# DueShield2.net
KiCad netlist of a schematic drawn in EAGLE
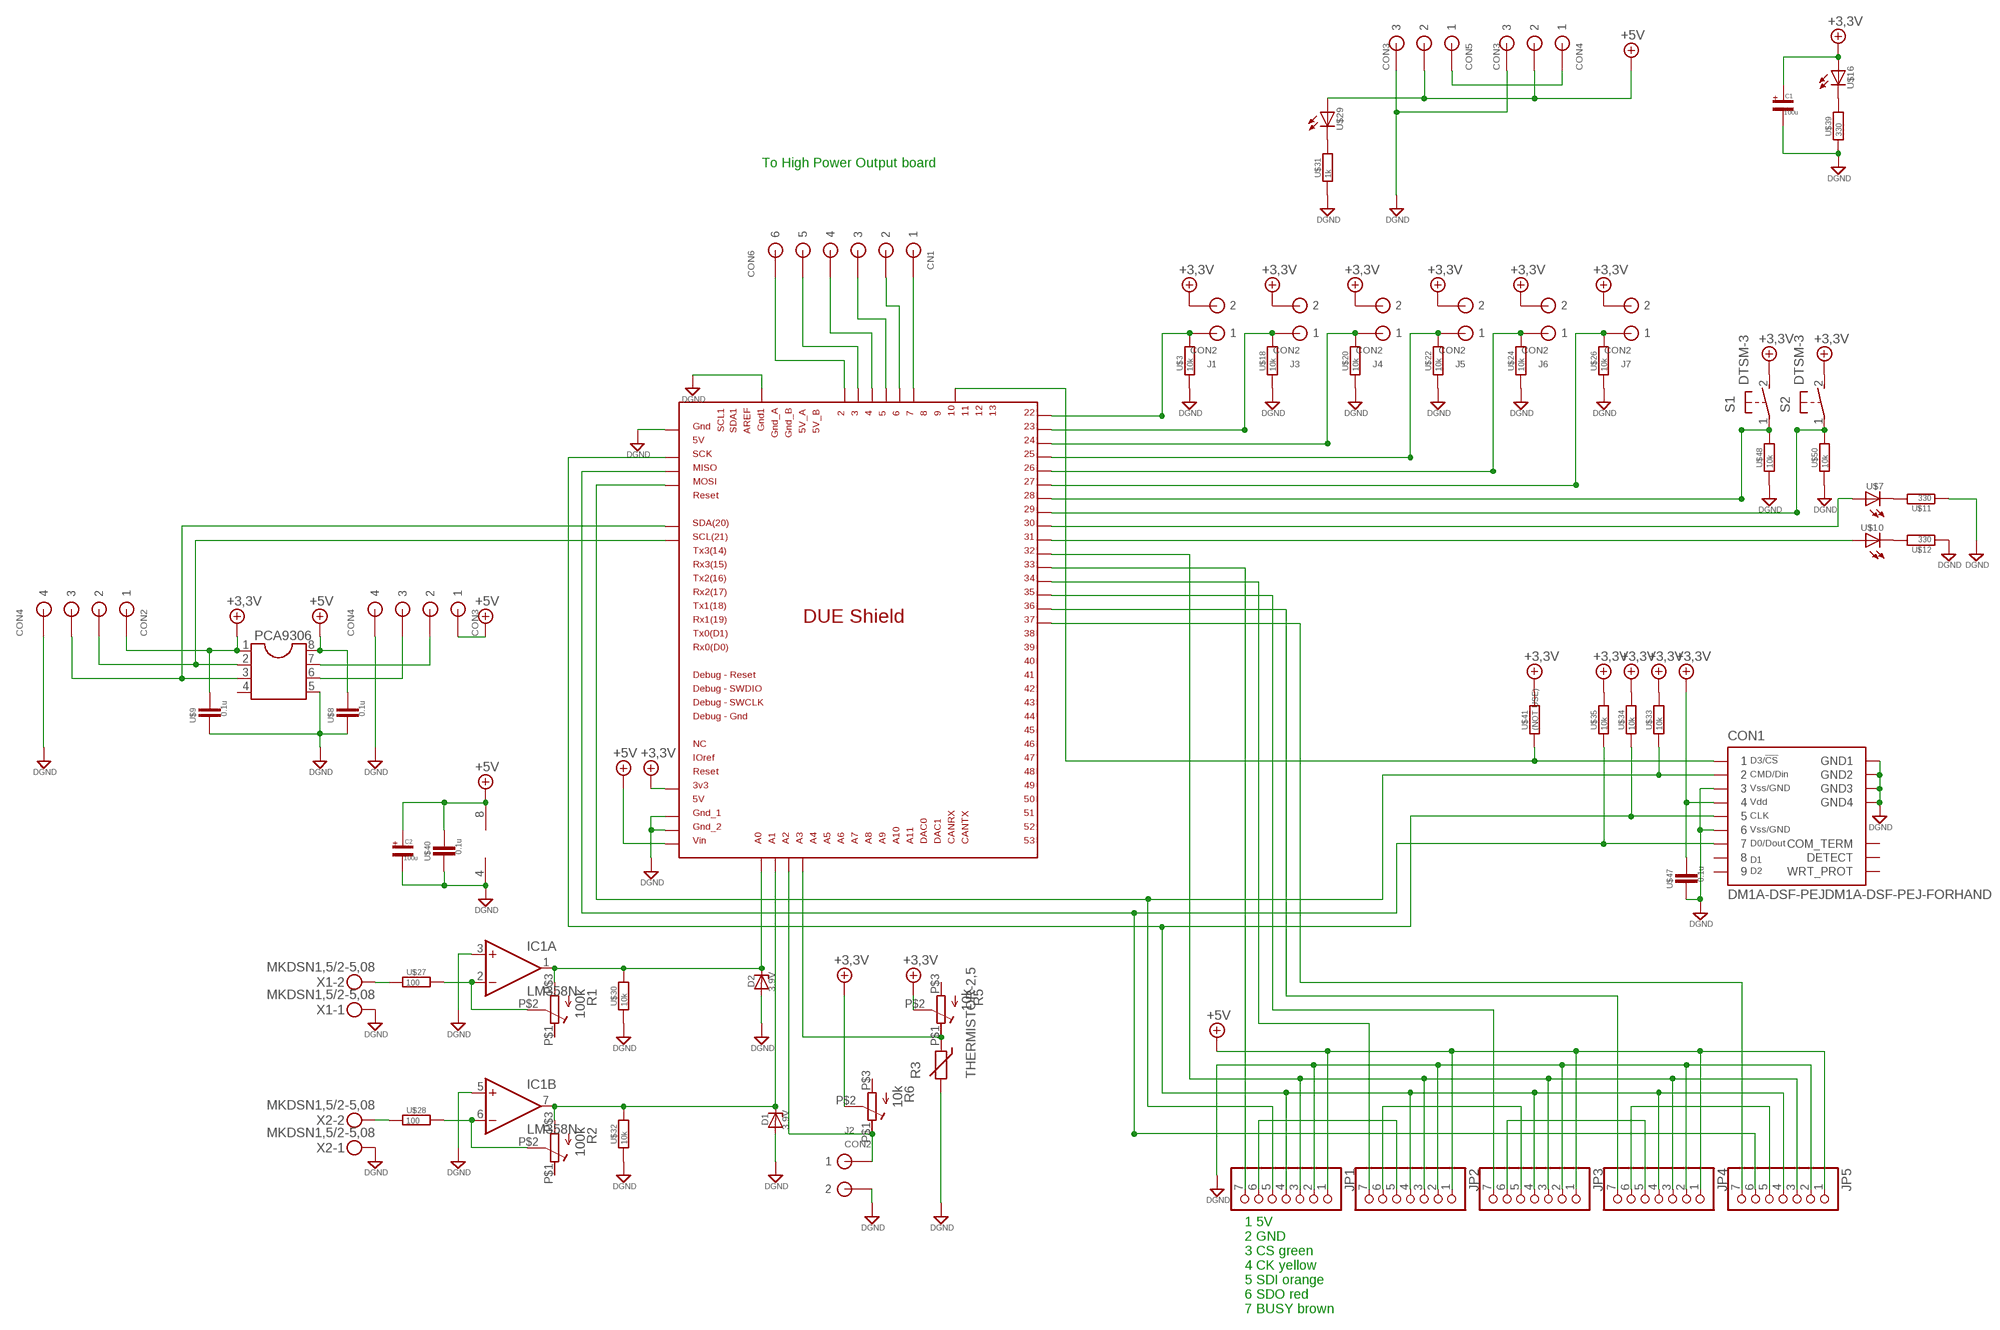
[diagram p0: schematic, sheet 1]

(export (version "E")
  (design (tool "Eeschema 10.0.6"))
  (components
    (comp (ref "C1")
      (value "100u")
      (footprint "eagle-import:D=1,φ=6")
      (libsource (lib "eagle-import") (part "コンデンサ(電解)E2.5-6"))
    )
    (comp (ref "C2")
      (value "100u")
      (footprint "eagle-import:D=1,φ=6")
      (libsource (lib "eagle-import") (part "コンデンサ(電解)E2.5-6"))
    )
    (comp (ref "CN1")
      (value "CON6")
      (footprint "eagle-import:CON6")
      (libsource (lib "eagle-import") (part "CON6"))
    )
    (comp (ref "CON1")
      (value "DM1A-DSF-PEJDM1A-DSF-PEJ-FORHAND")
      (footprint "eagle-import:DM1A-DSF-PEJ-FORHAND")
      (libsource (lib "eagle-import") (part "DM1A-DSF-PEJDM1A-DSF-PEJ-FORHAND"))
    )
    (comp (ref "CON2")
      (value "CON4")
      (footprint "eagle-import:CON4")
      (libsource (lib "eagle-import") (part "CON4"))
    )
    (comp (ref "CON3")
      (value "CON4")
      (footprint "eagle-import:CON4")
      (libsource (lib "eagle-import") (part "CON4"))
    )
    (comp (ref "CON4")
      (value "CON3")
      (footprint "eagle-import:CON3")
      (libsource (lib "eagle-import") (part "CON3"))
    )
    (comp (ref "CON5")
      (value "CON3")
      (footprint "eagle-import:CON3")
      (libsource (lib "eagle-import") (part "CON3"))
    )
    (comp (ref "D1")
      (value "3.9V")
      (footprint "eagle-import:SMD1206")
      (libsource (lib "eagle-import") (part "(汎用)ツェナーダイオード"))
    )
    (comp (ref "D2")
      (value "3.9V")
      (footprint "eagle-import:SMD1206")
      (libsource (lib "eagle-import") (part "(汎用)ツェナーダイオード"))
    )
    (comp (ref "IC1")
      (value "LM358N")
      (footprint "eagle-import:DIL08")
      (libsource (lib "eagle-import") (part "LM358N"))
    )
    (comp (ref "J1")
      (value "CON2")
      (footprint "eagle-import:CON2")
      (libsource (lib "eagle-import") (part "CON2"))
    )
    (comp (ref "J2")
      (value "CON2")
      (footprint "eagle-import:CON2")
      (libsource (lib "eagle-import") (part "CON2"))
    )
    (comp (ref "J3")
      (value "CON2")
      (footprint "eagle-import:CON2")
      (libsource (lib "eagle-import") (part "CON2"))
    )
    (comp (ref "J4")
      (value "CON2")
      (footprint "eagle-import:CON2")
      (libsource (lib "eagle-import") (part "CON2"))
    )
    (comp (ref "J5")
      (value "CON2")
      (footprint "eagle-import:CON2")
      (libsource (lib "eagle-import") (part "CON2"))
    )
    (comp (ref "J6")
      (value "CON2")
      (footprint "eagle-import:CON2")
      (libsource (lib "eagle-import") (part "CON2"))
    )
    (comp (ref "J7")
      (value "CON2")
      (footprint "eagle-import:CON2")
      (libsource (lib "eagle-import") (part "CON2"))
    )
    (comp (ref "JP1")
      (value "PINHD-1X7")
      (footprint "eagle-import:1X07")
      (libsource (lib "eagle-import") (part "PINHD-1X7"))
    )
    (comp (ref "JP2")
      (value "PINHD-1X7")
      (footprint "eagle-import:1X07")
      (libsource (lib "eagle-import") (part "PINHD-1X7"))
    )
    (comp (ref "JP3")
      (value "PINHD-1X7")
      (footprint "eagle-import:1X07")
      (libsource (lib "eagle-import") (part "PINHD-1X7"))
    )
    (comp (ref "JP4")
      (value "PINHD-1X7")
      (footprint "eagle-import:1X07")
      (libsource (lib "eagle-import") (part "PINHD-1X7"))
    )
    (comp (ref "JP5")
      (value "PINHD-1X7")
      (footprint "eagle-import:1X07")
      (libsource (lib "eagle-import") (part "PINHD-1X7"))
    )
    (comp (ref "PCA9306")
      (value "DIL8")
      (footprint "eagle-import:DIL08")
      (libsource (lib "eagle-import") (part "DIL8"))
    )
    (comp (ref "R1")
      (value "100k")
      (footprint "eagle-import:GF063PB")
      (libsource (lib "eagle-import") (part "抵抗(可変)"))
    )
    (comp (ref "R2")
      (value "100k")
      (footprint "eagle-import:GF063PB")
      (libsource (lib "eagle-import") (part "抵抗(可変)"))
    )
    (comp (ref "R3")
      (value "THERMISTOR-2,5")
      (footprint "eagle-import:RS-2,5")
      (libsource (lib "eagle-import") (part "THERMISTOR-2,5"))
    )
    (comp (ref "R5")
      (value "10k")
      (footprint "eagle-import:GF063PB")
      (libsource (lib "eagle-import") (part "抵抗(可変)"))
    )
    (comp (ref "R6")
      (value "10k")
      (footprint "eagle-import:GF063PB")
      (libsource (lib "eagle-import") (part "抵抗(可変)"))
    )
    (comp (ref "S1")
      (value "DTSM-3")
      (footprint "eagle-import:DTSM-3")
      (libsource (lib "eagle-import") (part "DTSM-3"))
    )
    (comp (ref "S2")
      (value "DTSM-3")
      (footprint "eagle-import:DTSM-3")
      (libsource (lib "eagle-import") (part "DTSM-3"))
    )
    (comp (ref "U$1")
      (value "DUE(3DPRINTER2)")
      (footprint "eagle-import:DUE(3DPRITNER2)")
      (libsource (lib "eagle-import") (part "DUE(3DPRINTER2)"))
    )
    (comp (ref "U$3")
      (value "10k")
      (footprint "eagle-import:0805(JIS2012)HAND")
      (libsource (lib "eagle-import") (part "抵抗0805"))
    )
    (comp (ref "U$7")
      (value "LED(砲弾型)3")
      (footprint "eagle-import:LED3MM")
      (libsource (lib "eagle-import") (part "LED(砲弾型)3"))
    )
    (comp (ref "U$8")
      (value "0.1u")
      (footprint "eagle-import:0805(JIS2012)HAND")
      (libsource (lib "eagle-import") (part "コンデンサ0805"))
    )
    (comp (ref "U$9")
      (value "0.1u")
      (footprint "eagle-import:0805(JIS2012)HAND")
      (libsource (lib "eagle-import") (part "コンデンサ0805"))
    )
    (comp (ref "U$10")
      (value "LED(砲弾型)3")
      (footprint "eagle-import:LED3MM")
      (libsource (lib "eagle-import") (part "LED(砲弾型)3"))
    )
    (comp (ref "U$11")
      (value "330")
      (footprint "eagle-import:0805(JIS2012)HAND")
      (libsource (lib "eagle-import") (part "抵抗0805"))
    )
    (comp (ref "U$12")
      (value "330")
      (footprint "eagle-import:0805(JIS2012)HAND")
      (libsource (lib "eagle-import") (part "抵抗0805"))
    )
    (comp (ref "U$16")
      (value "LED(砲弾型)3")
      (footprint "eagle-import:LED3MM")
      (libsource (lib "eagle-import") (part "LED(砲弾型)3"))
    )
    (comp (ref "U$18")
      (value "10k")
      (footprint "eagle-import:0805(JIS2012)HAND")
      (libsource (lib "eagle-import") (part "抵抗0805"))
    )
    (comp (ref "U$20")
      (value "10k")
      (footprint "eagle-import:0805(JIS2012)HAND")
      (libsource (lib "eagle-import") (part "抵抗0805"))
    )
    (comp (ref "U$22")
      (value "10k")
      (footprint "eagle-import:0805(JIS2012)HAND")
      (libsource (lib "eagle-import") (part "抵抗0805"))
    )
    (comp (ref "U$24")
      (value "10k")
      (footprint "eagle-import:0805(JIS2012)HAND")
      (libsource (lib "eagle-import") (part "抵抗0805"))
    )
    (comp (ref "U$26")
      (value "10k")
      (footprint "eagle-import:0805(JIS2012)HAND")
      (libsource (lib "eagle-import") (part "抵抗0805"))
    )
    (comp (ref "U$27")
      (value "100")
      (footprint "eagle-import:0805(JIS2012)HAND")
      (libsource (lib "eagle-import") (part "抵抗0805"))
    )
    (comp (ref "U$28")
      (value "100")
      (footprint "eagle-import:0805(JIS2012)HAND")
      (libsource (lib "eagle-import") (part "抵抗0805"))
    )
    (comp (ref "U$29")
      (value "LED(砲弾型)3")
      (footprint "eagle-import:LED3MM")
      (libsource (lib "eagle-import") (part "LED(砲弾型)3"))
    )
    (comp (ref "U$30")
      (value "10k")
      (footprint "eagle-import:0805(JIS2012)HAND")
      (libsource (lib "eagle-import") (part "抵抗0805"))
    )
    (comp (ref "U$31")
      (value "1k")
      (footprint "eagle-import:0805(JIS2012)HAND")
      (libsource (lib "eagle-import") (part "抵抗0805"))
    )
    (comp (ref "U$32")
      (value "10k")
      (footprint "eagle-import:0805(JIS2012)HAND")
      (libsource (lib "eagle-import") (part "抵抗0805"))
    )
    (comp (ref "U$33")
      (value "10k")
      (footprint "eagle-import:0805(JIS2012)HAND")
      (libsource (lib "eagle-import") (part "抵抗0805"))
    )
    (comp (ref "U$34")
      (value "10k")
      (footprint "eagle-import:0805(JIS2012)HAND")
      (libsource (lib "eagle-import") (part "抵抗0805"))
    )
    (comp (ref "U$35")
      (value "10k")
      (footprint "eagle-import:0805(JIS2012)HAND")
      (libsource (lib "eagle-import") (part "抵抗0805"))
    )
    (comp (ref "U$39")
      (value "330")
      (footprint "eagle-import:0805(JIS2012)HAND")
      (libsource (lib "eagle-import") (part "抵抗0805"))
    )
    (comp (ref "U$40")
      (value "0.1u")
      (footprint "eagle-import:0805(JIS2012)HAND")
      (libsource (lib "eagle-import") (part "コンデンサ0805"))
    )
    (comp (ref "U$41")
      (value "(NOT USE)")
      (footprint "eagle-import:0805(JIS2012)HAND")
      (libsource (lib "eagle-import") (part "抵抗0805"))
    )
    (comp (ref "U$47")
      (value "0.1u")
      (footprint "eagle-import:0805(JIS2012)HAND")
      (libsource (lib "eagle-import") (part "コンデンサ0805"))
    )
    (comp (ref "U$48")
      (value "10k")
      (footprint "eagle-import:0805(JIS2012)HAND")
      (libsource (lib "eagle-import") (part "抵抗0805"))
    )
    (comp (ref "U$50")
      (value "10k")
      (footprint "eagle-import:0805(JIS2012)HAND")
      (libsource (lib "eagle-import") (part "抵抗0805"))
    )
    (comp (ref "X1")
      (value "MKDSN1,5/2-5,08")
      (footprint "eagle-import:MKDSN1,5_2-5,08")
      (libsource (lib "eagle-import") (part "MKDSN1,5/2-5,08"))
    )
    (comp (ref "X2")
      (value "MKDSN1,5/2-5,08")
      (footprint "eagle-import:MKDSN1,5_2-5,08")
      (libsource (lib "eagle-import") (part "MKDSN1,5/2-5,08"))
    )
  )
  (nets
    (net (code "1") (name "+3,3V") (class "Default")
      (node (ref "C1") (pin "+") (pinfunction "+_+") (pintype "passive"))
      (node (ref "CON1") (pin "4") (pinfunction "4_4") (pintype "power_in"))
      (node (ref "CON2") (pin "P$1") (pinfunction "1_P$1") (pintype "bidirectional"))
      (node (ref "J1") (pin "P$2") (pinfunction "2_P$2") (pintype "bidirectional"))
      (node (ref "J3") (pin "P$2") (pinfunction "2_P$2") (pintype "bidirectional"))
      (node (ref "J4") (pin "P$2") (pinfunction "2_P$2") (pintype "bidirectional"))
      (node (ref "J5") (pin "P$2") (pinfunction "2_P$2") (pintype "bidirectional"))
      (node (ref "J6") (pin "P$2") (pinfunction "2_P$2") (pintype "bidirectional"))
      (node (ref "J7") (pin "P$2") (pinfunction "2_P$2") (pintype "bidirectional"))
      (node (ref "PCA9306") (pin "1") (pinfunction "1_1") (pintype "passive"))
      (node (ref "R5") (pin "P$2") (pinfunction "S_P$2") (pintype "passive"))
      (node (ref "R6") (pin "P$2") (pinfunction "S_P$2") (pintype "passive"))
      (node (ref "S1") (pin "2") (pinfunction "2_2") (pintype "passive"))
      (node (ref "S2") (pin "2") (pinfunction "2_2") (pintype "passive"))
      (node (ref "U$1") (pin "3V3") (pinfunction "3V3_3V3") (pintype "bidirectional"))
      (node (ref "U$16") (pin "A") (pinfunction "A_A") (pintype "passive"))
      (node (ref "U$33") (pin "2") (pinfunction "2_2") (pintype "passive"))
      (node (ref "U$34") (pin "2") (pinfunction "2_2") (pintype "passive"))
      (node (ref "U$35") (pin "2") (pinfunction "2_2") (pintype "passive"))
      (node (ref "U$41") (pin "2") (pinfunction "2_2") (pintype "passive"))
      (node (ref "U$47") (pin "1") (pinfunction "1_1") (pintype "passive"))
      (node (ref "U$9") (pin "1") (pinfunction "1_1") (pintype "passive"))
    )
    (net (code "2") (name "+5V") (class "Default")
      (node (ref "C2") (pin "+") (pinfunction "+_+") (pintype "passive"))
      (node (ref "CON3") (pin "P$1") (pinfunction "1_P$1") (pintype "bidirectional"))
      (node (ref "CON4") (pin "P$2") (pinfunction "2_P$2") (pintype "bidirectional"))
      (node (ref "CON5") (pin "P$2") (pinfunction "2_P$2") (pintype "bidirectional"))
      (node (ref "IC1") (pin "8") (pinfunction "V+_8") (pintype "power_in"))
      (node (ref "JP1") (pin "1") (pinfunction "1_1") (pintype "passive"))
      (node (ref "JP2") (pin "1") (pinfunction "1_1") (pintype "passive"))
      (node (ref "JP3") (pin "1") (pinfunction "1_1") (pintype "passive"))
      (node (ref "JP4") (pin "1") (pinfunction "1_1") (pintype "passive"))
      (node (ref "JP5") (pin "1") (pinfunction "1_1") (pintype "passive"))
      (node (ref "PCA9306") (pin "8") (pinfunction "8_8") (pintype "passive"))
      (node (ref "U$1") (pin "VIN") (pinfunction "VIN_VIN") (pintype "bidirectional"))
      (node (ref "U$29") (pin "A") (pinfunction "A_A") (pintype "passive"))
      (node (ref "U$40") (pin "1") (pinfunction "1_1") (pintype "passive"))
      (node (ref "U$8") (pin "1") (pinfunction "1_1") (pintype "passive"))
    )
    (net (code "3") (name "DGND") (class "Default")
      (node (ref "C1") (pin "-") (pinfunction "-_-") (pintype "passive"))
      (node (ref "C2") (pin "-") (pinfunction "-_-") (pintype "passive"))
      (node (ref "CON1") (pin "3") (pinfunction "3_3") (pintype "power_in"))
      (node (ref "CON1") (pin "6") (pinfunction "6_6") (pintype "power_in"))
      (node (ref "CON1") (pin "GND1") (pinfunction "GND1_GND1") (pintype "power_in"))
      (node (ref "CON1") (pin "GND2") (pinfunction "GND2_GND2") (pintype "power_in"))
      (node (ref "CON1") (pin "GND3") (pinfunction "GND3_GND3") (pintype "power_in"))
      (node (ref "CON1") (pin "GND4") (pinfunction "GND4_GND4") (pintype "power_in"))
      (node (ref "CON2") (pin "P$4") (pinfunction "4_P$4") (pintype "bidirectional"))
      (node (ref "CON3") (pin "P$4") (pinfunction "4_P$4") (pintype "bidirectional"))
      (node (ref "CON4") (pin "P$3") (pinfunction "3_P$3") (pintype "bidirectional"))
      (node (ref "CON5") (pin "P$3") (pinfunction "3_P$3") (pintype "bidirectional"))
      (node (ref "D1") (pin "2") (pinfunction "A_2") (pintype "passive"))
      (node (ref "D2") (pin "2") (pinfunction "A_2") (pintype "passive"))
      (node (ref "IC1") (pin "3") (pinfunction "+IN_3") (pintype "input"))
      (node (ref "IC1") (pin "4") (pinfunction "V-_4") (pintype "power_in"))
      (node (ref "IC1") (pin "5") (pinfunction "+IN_5") (pintype "input"))
      (node (ref "J2") (pin "P$2") (pinfunction "2_P$2") (pintype "bidirectional"))
      (node (ref "JP1") (pin "2") (pinfunction "2_2") (pintype "passive"))
      (node (ref "JP2") (pin "2") (pinfunction "2_2") (pintype "passive"))
      (node (ref "JP3") (pin "2") (pinfunction "2_2") (pintype "passive"))
      (node (ref "JP4") (pin "2") (pinfunction "2_2") (pintype "passive"))
      (node (ref "JP5") (pin "2") (pinfunction "2_2") (pintype "passive"))
      (node (ref "PCA9306") (pin "5") (pinfunction "5_5") (pintype "passive"))
      (node (ref "R3") (pin "2") (pinfunction "2_2") (pintype "passive"))
      (node (ref "U$1") (pin "5V_ICSP") (pinfunction "5V_ICSP_5V_ICSP") (pintype "bidirectional"))
      (node (ref "U$1") (pin "GND1") (pinfunction "GND1_GND1") (pintype "bidirectional"))
      (node (ref "U$1") (pin "GND_1") (pinfunction "GND_1_GND_1") (pintype "bidirectional"))
      (node (ref "U$1") (pin "GND_2") (pinfunction "GND_2_GND_2") (pintype "bidirectional"))
      (node (ref "U$11") (pin "1") (pinfunction "1_1") (pintype "passive"))
      (node (ref "U$12") (pin "1") (pinfunction "1_1") (pintype "passive"))
      (node (ref "U$18") (pin "1") (pinfunction "1_1") (pintype "passive"))
      (node (ref "U$20") (pin "1") (pinfunction "1_1") (pintype "passive"))
      (node (ref "U$22") (pin "1") (pinfunction "1_1") (pintype "passive"))
      (node (ref "U$24") (pin "1") (pinfunction "1_1") (pintype "passive"))
      (node (ref "U$26") (pin "1") (pinfunction "1_1") (pintype "passive"))
      (node (ref "U$3") (pin "1") (pinfunction "1_1") (pintype "passive"))
      (node (ref "U$30") (pin "1") (pinfunction "1_1") (pintype "passive"))
      (node (ref "U$31") (pin "1") (pinfunction "1_1") (pintype "passive"))
      (node (ref "U$32") (pin "1") (pinfunction "1_1") (pintype "passive"))
      (node (ref "U$39") (pin "1") (pinfunction "1_1") (pintype "passive"))
      (node (ref "U$40") (pin "2") (pinfunction "2_2") (pintype "passive"))
      (node (ref "U$47") (pin "2") (pinfunction "2_2") (pintype "passive"))
      (node (ref "U$48") (pin "1") (pinfunction "1_1") (pintype "passive"))
      (node (ref "U$50") (pin "1") (pinfunction "1_1") (pintype "passive"))
      (node (ref "U$8") (pin "2") (pinfunction "2_2") (pintype "passive"))
      (node (ref "U$9") (pin "2") (pinfunction "2_2") (pintype "passive"))
      (node (ref "X1") (pin "1") (pinfunction "KL_1") (pintype "passive"))
      (node (ref "X2") (pin "1") (pinfunction "KL_1") (pintype "passive"))
    )
    (net (code "4") (name "Net-(CN1-1)") (class "Default")
      (node (ref "CN1") (pin "P$1") (pinfunction "1_P$1") (pintype "bidirectional"))
      (node (ref "U$1") (pin "7") (pinfunction "7_7") (pintype "bidirectional"))
    )
    (net (code "5") (name "Net-(CN1-2)") (class "Default")
      (node (ref "CN1") (pin "P$2") (pinfunction "2_P$2") (pintype "bidirectional"))
      (node (ref "U$1") (pin "6") (pinfunction "6_6") (pintype "bidirectional"))
    )
    (net (code "6") (name "Net-(CN1-3)") (class "Default")
      (node (ref "CN1") (pin "P$3") (pinfunction "3_P$3") (pintype "bidirectional"))
      (node (ref "U$1") (pin "5") (pinfunction "5_5") (pintype "bidirectional"))
    )
    (net (code "7") (name "Net-(CN1-4)") (class "Default")
      (node (ref "CN1") (pin "P$4") (pinfunction "4_P$4") (pintype "bidirectional"))
      (node (ref "U$1") (pin "4") (pinfunction "4_4") (pintype "bidirectional"))
    )
    (net (code "8") (name "Net-(CN1-5)") (class "Default")
      (node (ref "CN1") (pin "P$5") (pinfunction "5_P$5") (pintype "bidirectional"))
      (node (ref "U$1") (pin "3") (pinfunction "3_3") (pintype "bidirectional"))
    )
    (net (code "9") (name "Net-(CN1-6)") (class "Default")
      (node (ref "CN1") (pin "P$6") (pinfunction "6_P$6") (pintype "bidirectional"))
      (node (ref "U$1") (pin "2") (pinfunction "2_2") (pintype "bidirectional"))
    )
    (net (code "10") (name "Net-(CON1-Pad1)") (class "Default")
      (node (ref "CON1") (pin "1") (pinfunction "1_1") (pintype "bidirectional"))
      (node (ref "U$1") (pin "10") (pinfunction "10_10") (pintype "bidirectional"))
      (node (ref "U$41") (pin "1") (pinfunction "1_1") (pintype "passive"))
    )
    (net (code "11") (name "Net-(CON1-Pad2)") (class "Default")
      (node (ref "CON1") (pin "2") (pinfunction "2_2") (pintype "input"))
      (node (ref "JP1") (pin "5") (pinfunction "5_5") (pintype "passive"))
      (node (ref "U$1") (pin "MOSI_ICSP") (pinfunction "MOSI_ICSP_MOSI_ICSP") (pintype "bidirectional"))
      (node (ref "U$33") (pin "1") (pinfunction "1_1") (pintype "passive"))
    )
    (net (code "12") (name "Net-(CON1-Pad5)") (class "Default")
      (node (ref "CON1") (pin "5") (pinfunction "5_5") (pintype "input"))
      (node (ref "JP1") (pin "4") (pinfunction "4_4") (pintype "passive"))
      (node (ref "JP2") (pin "4") (pinfunction "4_4") (pintype "passive"))
      (node (ref "JP3") (pin "4") (pinfunction "4_4") (pintype "passive"))
      (node (ref "JP4") (pin "4") (pinfunction "4_4") (pintype "passive"))
      (node (ref "JP5") (pin "4") (pinfunction "4_4") (pintype "passive"))
      (node (ref "U$1") (pin "SCK_ICSP") (pinfunction "SCK_ICSP_SCK_ICSP") (pintype "bidirectional"))
      (node (ref "U$34") (pin "1") (pinfunction "1_1") (pintype "passive"))
    )
    (net (code "13") (name "Net-(CON1-Pad7)") (class "Default")
      (node (ref "CON1") (pin "7") (pinfunction "7_7") (pintype "bidirectional"))
      (node (ref "JP5") (pin "6") (pinfunction "6_6") (pintype "passive"))
      (node (ref "U$1") (pin "MISO_ICSP") (pinfunction "MISO_ICSP_MISO_ICSP") (pintype "bidirectional"))
      (node (ref "U$35") (pin "1") (pinfunction "1_1") (pintype "passive"))
    )
    (net (code "14") (name "Net-(CON2-2)") (class "Default")
      (node (ref "CON2") (pin "P$2") (pinfunction "2_P$2") (pintype "bidirectional"))
      (node (ref "PCA9306") (pin "2") (pinfunction "2_2") (pintype "passive"))
      (node (ref "U$1") (pin "SCL") (pinfunction "SCL_SCL") (pintype "bidirectional"))
    )
    (net (code "15") (name "Net-(CON2-3)") (class "Default")
      (node (ref "CON2") (pin "P$3") (pinfunction "3_P$3") (pintype "bidirectional"))
      (node (ref "PCA9306") (pin "3") (pinfunction "3_3") (pintype "passive"))
      (node (ref "U$1") (pin "SDA") (pinfunction "SDA_SDA") (pintype "bidirectional"))
    )
    (net (code "16") (name "Net-(CON3-2)") (class "Default")
      (node (ref "CON3") (pin "P$2") (pinfunction "2_P$2") (pintype "bidirectional"))
      (node (ref "PCA9306") (pin "7") (pinfunction "7_7") (pintype "passive"))
    )
    (net (code "17") (name "Net-(CON3-3)") (class "Default")
      (node (ref "CON3") (pin "P$3") (pinfunction "3_P$3") (pintype "bidirectional"))
      (node (ref "PCA9306") (pin "6") (pinfunction "6_6") (pintype "passive"))
    )
    (net (code "18") (name "Net-(CON4-1)") (class "Default")
      (node (ref "CON4") (pin "P$1") (pinfunction "1_P$1") (pintype "bidirectional"))
      (node (ref "CON5") (pin "P$1") (pinfunction "1_P$1") (pintype "bidirectional"))
    )
    (net (code "19") (name "Net-(D1-C)") (class "Default")
      (node (ref "D1") (pin "1") (pinfunction "C_1") (pintype "passive"))
      (node (ref "IC1") (pin "7") (pinfunction "OUT_7") (pintype "output"))
      (node (ref "R2") (pin "P$3") (pinfunction "A_P$3") (pintype "passive"))
      (node (ref "U$1") (pin "A1") (pinfunction "A1_A1") (pintype "bidirectional"))
      (node (ref "U$32") (pin "2") (pinfunction "2_2") (pintype "passive"))
    )
    (net (code "20") (name "Net-(D2-C)") (class "Default")
      (node (ref "D2") (pin "1") (pinfunction "C_1") (pintype "passive"))
      (node (ref "IC1") (pin "1") (pinfunction "OUT_1") (pintype "output"))
      (node (ref "R1") (pin "P$3") (pinfunction "A_P$3") (pintype "passive"))
      (node (ref "U$1") (pin "A0") (pinfunction "A0_A0") (pintype "bidirectional"))
      (node (ref "U$30") (pin "2") (pinfunction "2_2") (pintype "passive"))
    )
    (net (code "21") (name "Net-(IC1A--IN)") (class "Default")
      (node (ref "IC1") (pin "2") (pinfunction "-IN_2") (pintype "input"))
      (node (ref "R1") (pin "P$2") (pinfunction "S_P$2") (pintype "passive"))
      (node (ref "U$27") (pin "2") (pinfunction "2_2") (pintype "passive"))
    )
    (net (code "22") (name "Net-(IC1B--IN)") (class "Default")
      (node (ref "IC1") (pin "6") (pinfunction "-IN_6") (pintype "input"))
      (node (ref "R2") (pin "P$2") (pinfunction "S_P$2") (pintype "passive"))
      (node (ref "U$28") (pin "2") (pinfunction "2_2") (pintype "passive"))
    )
    (net (code "23") (name "Net-(J1-1)") (class "Default")
      (node (ref "J1") (pin "P$1") (pinfunction "1_P$1") (pintype "bidirectional"))
      (node (ref "U$1") (pin "22") (pinfunction "22_22") (pintype "bidirectional"))
      (node (ref "U$3") (pin "2") (pinfunction "2_2") (pintype "passive"))
    )
    (net (code "24") (name "Net-(J2-1)") (class "Default")
      (node (ref "J2") (pin "P$1") (pinfunction "1_P$1") (pintype "bidirectional"))
      (node (ref "R6") (pin "P$1") (pinfunction "E_P$1") (pintype "passive"))
      (node (ref "U$1") (pin "A2") (pinfunction "A2_A2") (pintype "bidirectional"))
    )
    (net (code "25") (name "Net-(J3-1)") (class "Default")
      (node (ref "J3") (pin "P$1") (pinfunction "1_P$1") (pintype "bidirectional"))
      (node (ref "U$1") (pin "23") (pinfunction "23_23") (pintype "bidirectional"))
      (node (ref "U$18") (pin "2") (pinfunction "2_2") (pintype "passive"))
    )
    (net (code "26") (name "Net-(J4-1)") (class "Default")
      (node (ref "J4") (pin "P$1") (pinfunction "1_P$1") (pintype "bidirectional"))
      (node (ref "U$1") (pin "24") (pinfunction "24_24") (pintype "bidirectional"))
      (node (ref "U$20") (pin "2") (pinfunction "2_2") (pintype "passive"))
    )
    (net (code "27") (name "Net-(J5-1)") (class "Default")
      (node (ref "J5") (pin "P$1") (pinfunction "1_P$1") (pintype "bidirectional"))
      (node (ref "U$1") (pin "25") (pinfunction "25_25") (pintype "bidirectional"))
      (node (ref "U$22") (pin "2") (pinfunction "2_2") (pintype "passive"))
    )
    (net (code "28") (name "Net-(J6-1)") (class "Default")
      (node (ref "J6") (pin "P$1") (pinfunction "1_P$1") (pintype "bidirectional"))
      (node (ref "U$1") (pin "26") (pinfunction "26_26") (pintype "bidirectional"))
      (node (ref "U$24") (pin "2") (pinfunction "2_2") (pintype "passive"))
    )
    (net (code "29") (name "Net-(J7-1)") (class "Default")
      (node (ref "J7") (pin "P$1") (pinfunction "1_P$1") (pintype "bidirectional"))
      (node (ref "U$1") (pin "27") (pinfunction "27_27") (pintype "bidirectional"))
      (node (ref "U$26") (pin "2") (pinfunction "2_2") (pintype "passive"))
    )
    (net (code "30") (name "Net-(JP1-Pad3)") (class "Default")
      (node (ref "JP1") (pin "3") (pinfunction "3_3") (pintype "passive"))
      (node (ref "JP2") (pin "3") (pinfunction "3_3") (pintype "passive"))
      (node (ref "JP3") (pin "3") (pinfunction "3_3") (pintype "passive"))
      (node (ref "JP4") (pin "3") (pinfunction "3_3") (pintype "passive"))
      (node (ref "JP5") (pin "3") (pinfunction "3_3") (pintype "passive"))
      (node (ref "U$1") (pin "32") (pinfunction "32_32") (pintype "bidirectional"))
    )
    (net (code "31") (name "Net-(JP1-Pad6)") (class "Default")
      (node (ref "JP1") (pin "6") (pinfunction "6_6") (pintype "passive"))
      (node (ref "JP2") (pin "5") (pinfunction "5_5") (pintype "passive"))
    )
    (net (code "32") (name "Net-(JP1-Pad7)") (class "Default")
      (node (ref "JP1") (pin "7") (pinfunction "7_7") (pintype "passive"))
      (node (ref "U$1") (pin "33") (pinfunction "33_33") (pintype "bidirectional"))
    )
    (net (code "33") (name "Net-(JP2-Pad6)") (class "Default")
      (node (ref "JP2") (pin "6") (pinfunction "6_6") (pintype "passive"))
      (node (ref "JP3") (pin "5") (pinfunction "5_5") (pintype "passive"))
    )
    (net (code "34") (name "Net-(JP2-Pad7)") (class "Default")
      (node (ref "JP2") (pin "7") (pinfunction "7_7") (pintype "passive"))
      (node (ref "U$1") (pin "34") (pinfunction "34_34") (pintype "bidirectional"))
    )
    (net (code "35") (name "Net-(JP3-Pad6)") (class "Default")
      (node (ref "JP3") (pin "6") (pinfunction "6_6") (pintype "passive"))
      (node (ref "JP4") (pin "5") (pinfunction "5_5") (pintype "passive"))
    )
    (net (code "36") (name "Net-(JP3-Pad7)") (class "Default")
      (node (ref "JP3") (pin "7") (pinfunction "7_7") (pintype "passive"))
      (node (ref "U$1") (pin "35") (pinfunction "35_35") (pintype "bidirectional"))
    )
    (net (code "37") (name "Net-(JP4-Pad6)") (class "Default")
      (node (ref "JP4") (pin "6") (pinfunction "6_6") (pintype "passive"))
      (node (ref "JP5") (pin "5") (pinfunction "5_5") (pintype "passive"))
    )
    (net (code "38") (name "Net-(JP4-Pad7)") (class "Default")
      (node (ref "JP4") (pin "7") (pinfunction "7_7") (pintype "passive"))
      (node (ref "U$1") (pin "36") (pinfunction "36_36") (pintype "bidirectional"))
    )
    (net (code "39") (name "Net-(JP5-Pad7)") (class "Default")
      (node (ref "JP5") (pin "7") (pinfunction "7_7") (pintype "passive"))
      (node (ref "U$1") (pin "37") (pinfunction "37_37") (pintype "bidirectional"))
    )
    (net (code "40") (name "Net-(R5-E)") (class "Default")
      (node (ref "R3") (pin "1") (pinfunction "1_1") (pintype "passive"))
      (node (ref "R5") (pin "P$1") (pinfunction "E_P$1") (pintype "passive"))
      (node (ref "U$1") (pin "A3") (pinfunction "A3_A3") (pintype "bidirectional"))
    )
    (net (code "41") (name "Net-(S1-Pad1)") (class "Default")
      (node (ref "S1") (pin "1") (pinfunction "1_1") (pintype "passive"))
      (node (ref "U$1") (pin "28") (pinfunction "28_28") (pintype "bidirectional"))
      (node (ref "U$48") (pin "2") (pinfunction "2_2") (pintype "passive"))
    )
    (net (code "42") (name "Net-(S2-Pad1)") (class "Default")
      (node (ref "S2") (pin "1") (pinfunction "1_1") (pintype "passive"))
      (node (ref "U$1") (pin "29") (pinfunction "29_29") (pintype "bidirectional"))
      (node (ref "U$50") (pin "2") (pinfunction "2_2") (pintype "passive"))
    )
    (net (code "43") (name "Net-(U$1-Pad30)") (class "Default")
      (node (ref "U$1") (pin "30") (pinfunction "30_30") (pintype "bidirectional"))
      (node (ref "U$7") (pin "A") (pinfunction "A_A") (pintype "passive"))
    )
    (net (code "44") (name "Net-(U$1-Pad31)") (class "Default")
      (node (ref "U$1") (pin "31") (pinfunction "31_31") (pintype "bidirectional"))
      (node (ref "U$10") (pin "A") (pinfunction "A_A") (pintype "passive"))
    )
    (net (code "45") (name "Net-(U$10-PadK)") (class "Default")
      (node (ref "U$10") (pin "K") (pinfunction "K_K") (pintype "passive"))
      (node (ref "U$12") (pin "2") (pinfunction "2_2") (pintype "passive"))
    )
    (net (code "46") (name "Net-(U$11-Pad2)") (class "Default")
      (node (ref "U$11") (pin "2") (pinfunction "2_2") (pintype "passive"))
      (node (ref "U$7") (pin "K") (pinfunction "K_K") (pintype "passive"))
    )
    (net (code "47") (name "Net-(U$16-PadK)") (class "Default")
      (node (ref "U$16") (pin "K") (pinfunction "K_K") (pintype "passive"))
      (node (ref "U$39") (pin "2") (pinfunction "2_2") (pintype "passive"))
    )
    (net (code "48") (name "Net-(U$29-PadK)") (class "Default")
      (node (ref "U$29") (pin "K") (pinfunction "K_K") (pintype "passive"))
      (node (ref "U$31") (pin "2") (pinfunction "2_2") (pintype "passive"))
    )
    (net (code "49") (name "Net-(X1B-KL)") (class "Default")
      (node (ref "U$27") (pin "1") (pinfunction "1_1") (pintype "passive"))
      (node (ref "X1") (pin "2") (pinfunction "KL_2") (pintype "passive"))
    )
    (net (code "50") (name "Net-(X2B-KL)") (class "Default")
      (node (ref "U$28") (pin "1") (pinfunction "1_1") (pintype "passive"))
      (node (ref "X2") (pin "2") (pinfunction "KL_2") (pintype "passive"))
    )
    (net (code "51") (name "unconnected-(CON1-Pad8)") (class "Default")
      (node (ref "CON1") (pin "8") (pinfunction "8_8") (pintype "bidirectional"))
    )
    (net (code "52") (name "unconnected-(CON1-Pad9)") (class "Default")
      (node (ref "CON1") (pin "9") (pinfunction "9_9") (pintype "bidirectional"))
    )
    (net (code "53") (name "unconnected-(CON1-PadCOM_TERM)") (class "Default")
      (node (ref "CON1") (pin "COM_TERM") (pinfunction "COM_TERM_COM_TERM") (pintype "output"))
    )
    (net (code "54") (name "unconnected-(CON1-PadDETECT)") (class "Default")
      (node (ref "CON1") (pin "DETECT") (pinfunction "DETECT_DETECT") (pintype "output"))
    )
    (net (code "55") (name "unconnected-(CON1-PadWRT_PROT)") (class "Default")
      (node (ref "CON1") (pin "WRT_PROT") (pinfunction "WRT_PROT_WRT_PROT") (pintype "output"))
    )
    (net (code "56") (name "unconnected-(PCA9306-Pad4)") (class "Default")
      (node (ref "PCA9306") (pin "4") (pinfunction "4_4") (pintype "passive"))
    )
    (net (code "57") (name "unconnected-(R1-E-PadP$1)") (class "Default")
      (node (ref "R1") (pin "P$1") (pinfunction "E_P$1") (pintype "passive"))
    )
    (net (code "58") (name "unconnected-(R2-E-PadP$1)") (class "Default")
      (node (ref "R2") (pin "P$1") (pinfunction "E_P$1") (pintype "passive"))
    )
    (net (code "59") (name "unconnected-(R5-A-PadP$3)") (class "Default")
      (node (ref "R5") (pin "P$3") (pinfunction "A_P$3") (pintype "passive"))
    )
    (net (code "60") (name "unconnected-(R6-A-PadP$3)") (class "Default")
      (node (ref "R6") (pin "P$3") (pinfunction "A_P$3") (pintype "passive"))
    )
  )
)
